# FPGA_POWER.net
KiCad netlist of a schematic drawn in Altium Designer
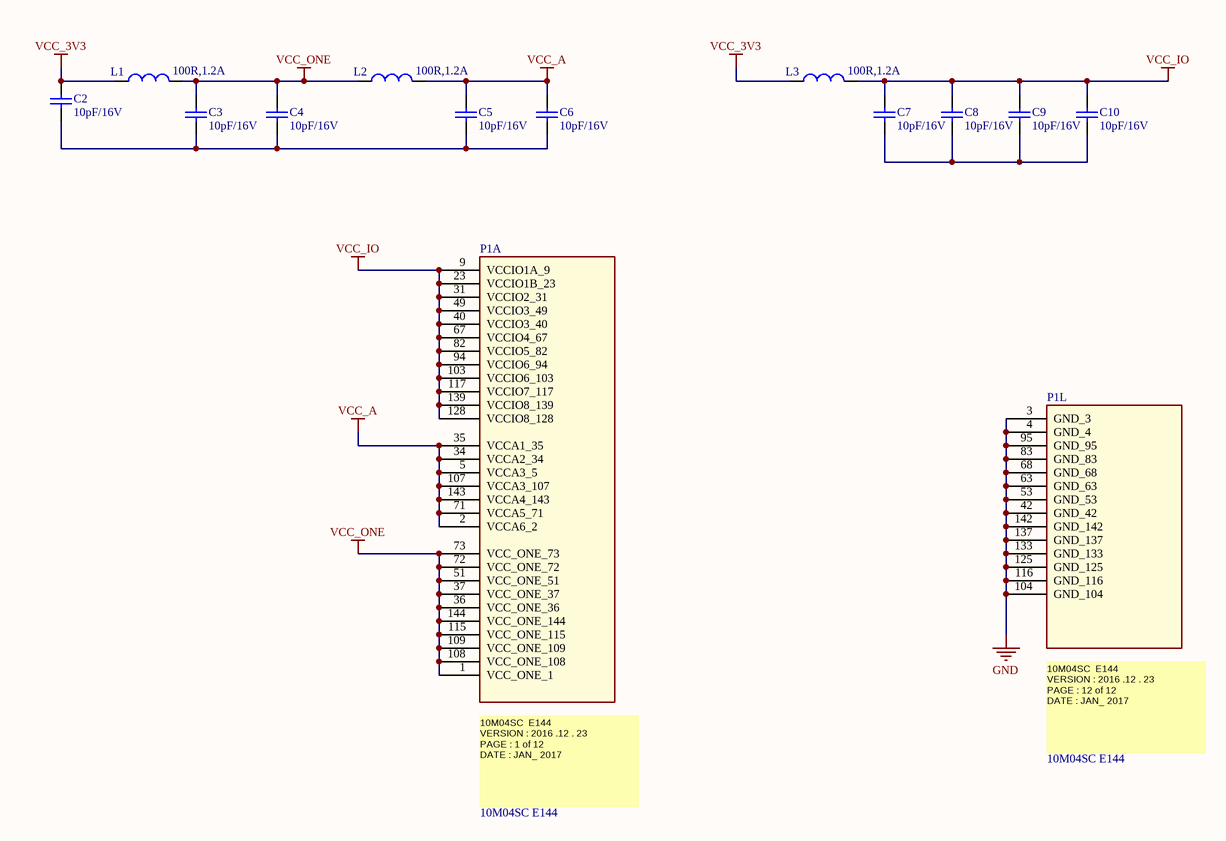
[diagram p0: FPGA_POWER.SchDoc]

(export (version "E")
  (design (tool "Eeschema 10.0.6"))
  (components
    (comp (ref "C2")
      (value "10pF/16V")
      (footprint "RAD-0.3")
      (description "Capacitor")
      (fields (field (name "PUBLISHER") "Altium Limited"))
      (libsource (lib "Miscellaneous Devices") (part "Cap"))
    )
    (comp (ref "C3")
      (value "10pF/16V")
      (footprint "RAD-0.3")
      (description "Capacitor")
      (fields (field (name "PUBLISHER") "Altium Limited"))
      (libsource (lib "Miscellaneous Devices") (part "Cap"))
    )
    (comp (ref "C4")
      (value "10pF/16V")
      (footprint "RAD-0.3")
      (description "Capacitor")
      (fields (field (name "PUBLISHER") "Altium Limited"))
      (libsource (lib "Miscellaneous Devices") (part "Cap"))
    )
    (comp (ref "C5")
      (value "10pF/16V")
      (footprint "RAD-0.3")
      (description "Capacitor")
      (fields (field (name "PUBLISHER") "Altium Limited"))
      (libsource (lib "Miscellaneous Devices") (part "Cap"))
    )
    (comp (ref "C6")
      (value "10pF/16V")
      (footprint "RAD-0.3")
      (description "Capacitor")
      (fields (field (name "PUBLISHER") "Altium Limited"))
      (libsource (lib "Miscellaneous Devices") (part "Cap"))
    )
    (comp (ref "C7")
      (value "10pF/16V")
      (footprint "RAD-0.3")
      (description "Capacitor")
      (fields (field (name "PUBLISHER") "Altium Limited"))
      (libsource (lib "Miscellaneous Devices") (part "Cap"))
    )
    (comp (ref "C8")
      (value "10pF/16V")
      (footprint "RAD-0.3")
      (description "Capacitor")
      (fields (field (name "PUBLISHER") "Altium Limited"))
      (libsource (lib "Miscellaneous Devices") (part "Cap"))
    )
    (comp (ref "C9")
      (value "10pF/16V")
      (footprint "RAD-0.3")
      (description "Capacitor")
      (fields (field (name "PUBLISHER") "Altium Limited"))
      (libsource (lib "Miscellaneous Devices") (part "Cap"))
    )
    (comp (ref "C10")
      (value "10pF/16V")
      (footprint "RAD-0.3")
      (description "Capacitor")
      (fields (field (name "PUBLISHER") "Altium Limited"))
      (libsource (lib "Miscellaneous Devices") (part "Cap"))
    )
    (comp (ref "L1")
      (value "100R,1.2A")
      (footprint "0603_IND")
      (description "Ferrite Beads 100ohms 1A 60mOhms 0603 Ferrite Chip")
      (fields (field (name "MANUFACTURER") "TDK") (field (name "STOCKIEST PART NO") "810-MPZ1608D101BTA00"))
      (libsource (lib "de20") (part "0805_IND"))
    )
    (comp (ref "L2")
      (value "100R,1.2A")
      (footprint "0603_IND")
      (description "Ferrite Beads 100ohms 1A 60mOhms 0603 Ferrite Chip")
      (fields (field (name "MANUFACTURER") "TDK") (field (name "STOCKIEST PART NO") "810-MPZ1608D101BTA00"))
      (libsource (lib "de20") (part "0805_IND"))
    )
    (comp (ref "L3")
      (value "100R,1.2A")
      (footprint "0603_IND")
      (description "Ferrite Beads 100ohms 1A 60mOhms 0603 Ferrite Chip")
      (fields (field (name "MANUFACTURER") "TDK") (field (name "STOCKIEST PART NO") "810-MPZ1608D101BTA00"))
      (libsource (lib "de20") (part "0805_IND"))
    )
    (comp (ref "P1") (value "10M04SC E144") (libsource (lib "10m04sc_Library") (part "10M04SC E144")))
  )
  (nets
    (net (code "1") (name "GND") (class "Default")
      (node (ref "P1") (pin "104") (pinfunction "GND_104_104") (pintype "power_in"))
      (node (ref "P1") (pin "116") (pinfunction "GND_116_116") (pintype "power_in"))
      (node (ref "P1") (pin "125") (pinfunction "GND_125_125") (pintype "power_in"))
      (node (ref "P1") (pin "133") (pinfunction "GND_133_133") (pintype "power_in"))
      (node (ref "P1") (pin "137") (pinfunction "GND_137_137") (pintype "power_in"))
      (node (ref "P1") (pin "142") (pinfunction "GND_142_142") (pintype "power_in"))
      (node (ref "P1") (pin "3") (pinfunction "GND_3_3") (pintype "power_in"))
      (node (ref "P1") (pin "4") (pinfunction "GND_4_4") (pintype "power_in"))
      (node (ref "P1") (pin "42") (pinfunction "GND_42_42") (pintype "power_in"))
      (node (ref "P1") (pin "53") (pinfunction "GND_53_53") (pintype "power_in"))
      (node (ref "P1") (pin "63") (pinfunction "GND_63_63") (pintype "power_in"))
      (node (ref "P1") (pin "68") (pinfunction "GND_68_68") (pintype "power_in"))
      (node (ref "P1") (pin "83") (pinfunction "GND_83_83") (pintype "power_in"))
      (node (ref "P1") (pin "95") (pinfunction "GND_95_95") (pintype "power_in"))
    )
    (net (code "2") (name "Net-(C2-Pad2)") (class "Default")
      (node (ref "C2") (pin "2") (pinfunction "2_2") (pintype "passive"))
      (node (ref "C3") (pin "2") (pinfunction "2_2") (pintype "passive"))
      (node (ref "C4") (pin "2") (pinfunction "2_2") (pintype "passive"))
      (node (ref "C5") (pin "2") (pinfunction "2_2") (pintype "passive"))
      (node (ref "C6") (pin "2") (pinfunction "2_2") (pintype "passive"))
    )
    (net (code "3") (name "Net-(C10-Pad2)") (class "Default")
      (node (ref "C10") (pin "2") (pinfunction "2_2") (pintype "passive"))
      (node (ref "C7") (pin "2") (pinfunction "2_2") (pintype "passive"))
      (node (ref "C8") (pin "2") (pinfunction "2_2") (pintype "passive"))
      (node (ref "C9") (pin "2") (pinfunction "2_2") (pintype "passive"))
    )
    (net (code "4") (name "VCC_3V3") (class "Default")
      (node (ref "C2") (pin "1") (pinfunction "1_1") (pintype "passive"))
      (node (ref "L1") (pin "1") (pinfunction "1_1") (pintype "passive"))
      (node (ref "L3") (pin "1") (pinfunction "1_1") (pintype "passive"))
    )
    (net (code "5") (name "VCC_A") (class "Default")
      (node (ref "C5") (pin "1") (pinfunction "1_1") (pintype "passive"))
      (node (ref "C6") (pin "1") (pinfunction "1_1") (pintype "passive"))
      (node (ref "L2") (pin "2") (pinfunction "2_2") (pintype "passive"))
      (node (ref "P1") (pin "107") (pinfunction "VCCA3_107_107") (pintype "power_in"))
      (node (ref "P1") (pin "143") (pinfunction "VCCA4_143_143") (pintype "power_in"))
      (node (ref "P1") (pin "2") (pinfunction "VCCA6_2_2") (pintype "power_in"))
      (node (ref "P1") (pin "34") (pinfunction "VCCA2_34_34") (pintype "power_in"))
      (node (ref "P1") (pin "35") (pinfunction "VCCA1_35_35") (pintype "power_in"))
      (node (ref "P1") (pin "5") (pinfunction "VCCA3_5_5") (pintype "power_in"))
      (node (ref "P1") (pin "71") (pinfunction "VCCA5_71_71") (pintype "power_in"))
    )
    (net (code "6") (name "VCC_IO") (class "Default")
      (node (ref "C10") (pin "1") (pinfunction "1_1") (pintype "passive"))
      (node (ref "C7") (pin "1") (pinfunction "1_1") (pintype "passive"))
      (node (ref "C8") (pin "1") (pinfunction "1_1") (pintype "passive"))
      (node (ref "C9") (pin "1") (pinfunction "1_1") (pintype "passive"))
      (node (ref "L3") (pin "2") (pinfunction "2_2") (pintype "passive"))
      (node (ref "P1") (pin "103") (pinfunction "VCCIO6_103_103") (pintype "power_in"))
      (node (ref "P1") (pin "117") (pinfunction "VCCIO7_117_117") (pintype "power_in"))
      (node (ref "P1") (pin "128") (pinfunction "VCCIO8_128_128") (pintype "power_in"))
      (node (ref "P1") (pin "139") (pinfunction "VCCIO8_139_139") (pintype "power_in"))
      (node (ref "P1") (pin "23") (pinfunction "VCCIO1B_23_23") (pintype "power_in"))
      (node (ref "P1") (pin "31") (pinfunction "VCCIO2_31_31") (pintype "power_in"))
      (node (ref "P1") (pin "40") (pinfunction "VCCIO3_40_40") (pintype "power_in"))
      (node (ref "P1") (pin "49") (pinfunction "VCCIO3_49_49") (pintype "power_in"))
      (node (ref "P1") (pin "67") (pinfunction "VCCIO4_67_67") (pintype "power_in"))
      (node (ref "P1") (pin "82") (pinfunction "VCCIO5_82_82") (pintype "power_in"))
      (node (ref "P1") (pin "9") (pinfunction "VCCIO1A_9_9") (pintype "power_in"))
      (node (ref "P1") (pin "94") (pinfunction "VCCIO6_94_94") (pintype "power_in"))
    )
    (net (code "7") (name "VCC_ONE") (class "Default")
      (node (ref "C3") (pin "1") (pinfunction "1_1") (pintype "passive"))
      (node (ref "C4") (pin "1") (pinfunction "1_1") (pintype "passive"))
      (node (ref "L1") (pin "2") (pinfunction "2_2") (pintype "passive"))
      (node (ref "L2") (pin "1") (pinfunction "1_1") (pintype "passive"))
      (node (ref "P1") (pin "1") (pinfunction "VCC_ONE_1_1") (pintype "power_in"))
      (node (ref "P1") (pin "108") (pinfunction "VCC_ONE_108_108") (pintype "power_in"))
      (node (ref "P1") (pin "109") (pinfunction "VCC_ONE_109_109") (pintype "power_in"))
      (node (ref "P1") (pin "115") (pinfunction "VCC_ONE_115_115") (pintype "power_in"))
      (node (ref "P1") (pin "144") (pinfunction "VCC_ONE_144_144") (pintype "power_in"))
      (node (ref "P1") (pin "36") (pinfunction "VCC_ONE_36_36") (pintype "power_in"))
      (node (ref "P1") (pin "37") (pinfunction "VCC_ONE_37_37") (pintype "power_in"))
      (node (ref "P1") (pin "51") (pinfunction "VCC_ONE_51_51") (pintype "power_in"))
      (node (ref "P1") (pin "72") (pinfunction "VCC_ONE_72_72") (pintype "power_in"))
      (node (ref "P1") (pin "73") (pinfunction "VCC_ONE_73_73") (pintype "power_in"))
    )
  )
)
